# modul.net
KiCad netlist of a schematic drawn in Altium Designer
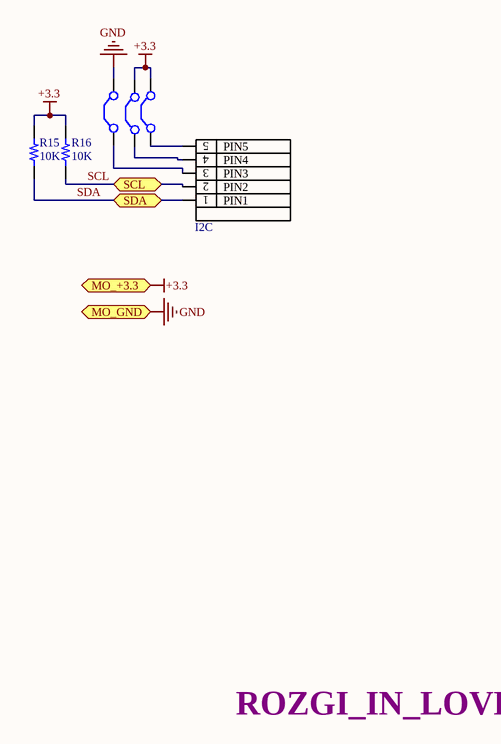
[diagram p0: modul.SchDoc]

(export (version "E")
  (design (tool "Eeschema 10.0.6"))
  (components
    (comp (ref "I2C")
      (value "Ğàçú¸ì PLS-5")
      (footprint "JST B5B-PH-K")
      (description "Male, 5 pin single in line, 2.54")
      (libsource (lib "header") (part "HDR 1x5"))
    )
    (comp (ref "JS1")
      (value "Ïåğåìû÷êà SMD 1206")
      (footprint "Jumper SMD Small")
      (description "Ïåğåìû÷êà")
      (libsource (lib "genel") (part "Jumper"))
    )
    (comp (ref "JS2")
      (value "Ïåğåìû÷êà SMD 1206")
      (footprint "Jumper SMD Small")
      (description "Ïåğåìû÷êà")
      (libsource (lib "genel") (part "Jumper"))
    )
    (comp (ref "JS3")
      (value "Ïåğåìû÷êà SMD 1206")
      (footprint "Jumper SMD Small")
      (description "Ïåğåìû÷êà")
      (libsource (lib "genel") (part "Jumper"))
    )
    (comp (ref "R15")
      (value "10K")
      (footprint "RES 0603")
      (description "RES")
      (libsource (lib "genel") (part "RES"))
    )
    (comp (ref "R16")
      (value "10K")
      (footprint "RES 0603")
      (description "RES")
      (libsource (lib "genel") (part "RES"))
    )
  )
  (nets
    (net (code "1") (name "+3.3") (class "Default")
      (node (ref "JS2") (pin "2") (pinfunction "2_2") (pintype "passive"))
      (node (ref "JS3") (pin "2") (pinfunction "2_2") (pintype "passive"))
      (node (ref "R15") (pin "2") (pinfunction "2_2") (pintype "passive"))
      (node (ref "R16") (pin "2") (pinfunction "2_2") (pintype "passive"))
    )
    (net (code "2") (name "/SCL") (class "Default")
      (node (ref "I2C") (pin "1") (pinfunction "PIN2_1") (pintype "passive"))
      (node (ref "R16") (pin "1") (pinfunction "1_1") (pintype "passive"))
    )
    (net (code "3") (name "/SDA") (class "Default")
      (node (ref "I2C") (pin "2") (pinfunction "PIN1_2") (pintype "passive"))
      (node (ref "R15") (pin "1") (pinfunction "1_1") (pintype "passive"))
    )
    (net (code "4") (name "GND") (class "Default")
      (node (ref "JS1") (pin "2") (pinfunction "2_2") (pintype "passive"))
    )
    (net (code "5") (name "Net-(I2C-PIN3)") (class "Default")
      (node (ref "I2C") (pin "3") (pinfunction "PIN3_3") (pintype "passive"))
      (node (ref "JS1") (pin "1") (pinfunction "1_1") (pintype "passive"))
    )
    (net (code "6") (name "Net-(I2C-PIN4)") (class "Default")
      (node (ref "I2C") (pin "4") (pinfunction "PIN4_4") (pintype "passive"))
      (node (ref "JS3") (pin "1") (pinfunction "1_1") (pintype "passive"))
    )
    (net (code "7") (name "Net-(I2C-PIN5)") (class "Default")
      (node (ref "I2C") (pin "5") (pinfunction "PIN5_5") (pintype "passive"))
      (node (ref "JS2") (pin "1") (pinfunction "1_1") (pintype "passive"))
    )
  )
)
